# usb_hub.net
KiCad netlist of a schematic drawn in Altium Designer
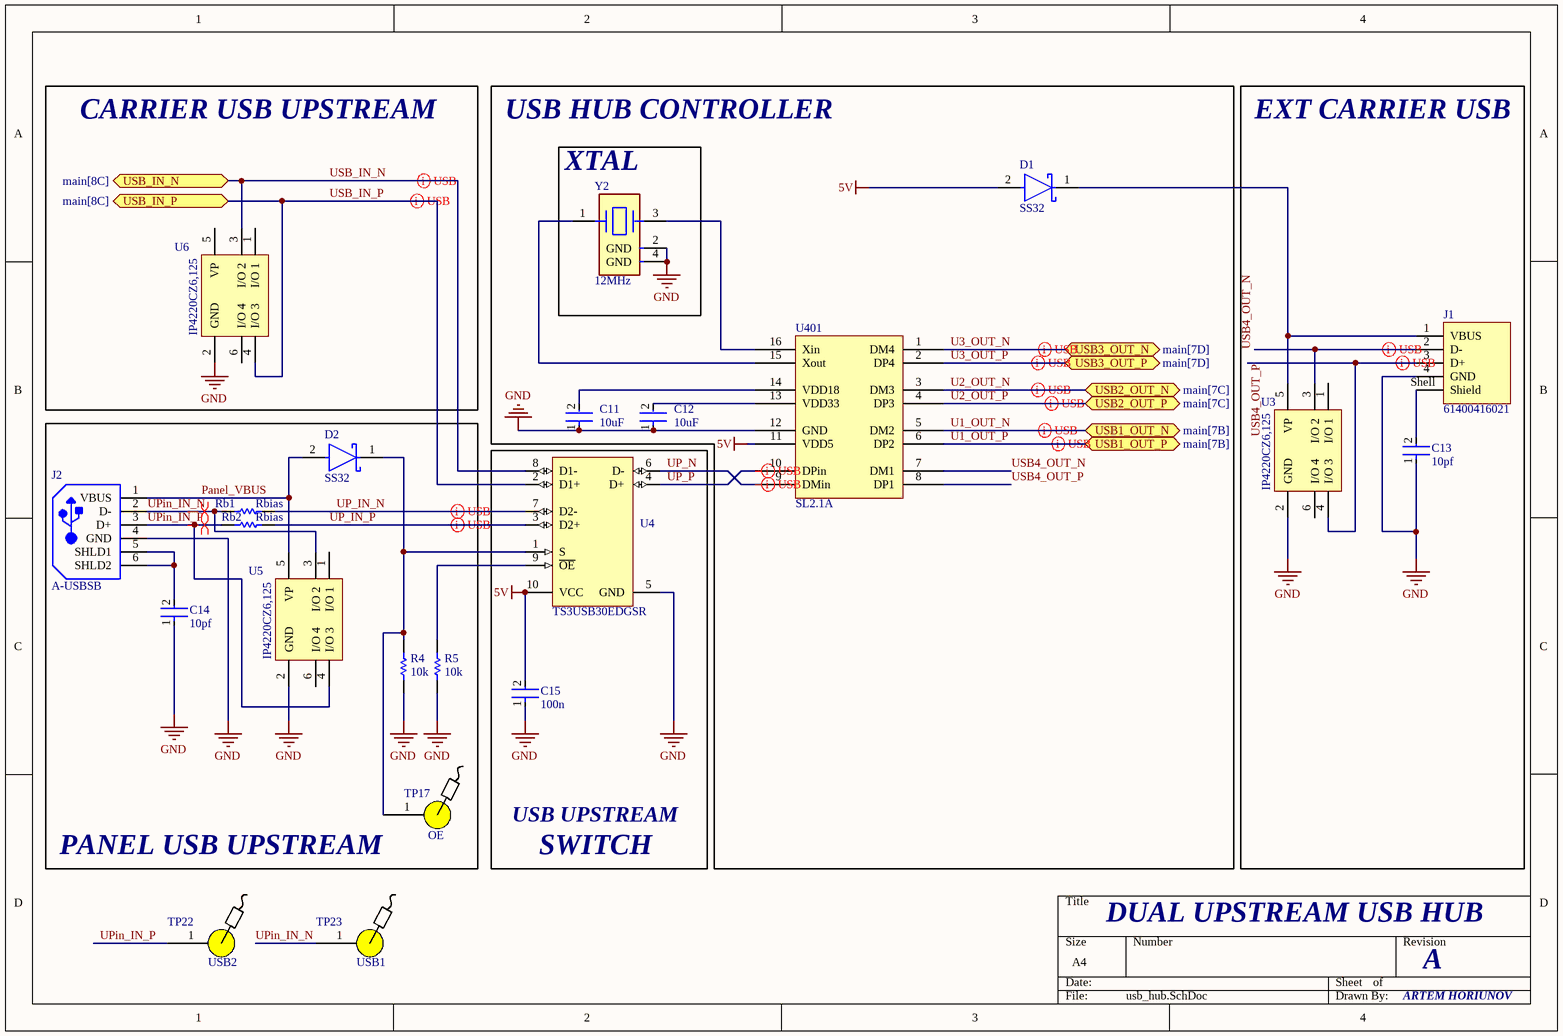
[diagram p0: usb_hub.SchDoc]

(export (version "E")
  (design (tool "Eeschema 10.0.6"))
  (components
    (comp (ref "C11")
      (value "10uF")
      (footprint "FP-C0603C-CF-MFG")
      (description "CAP CER 0.1UF 50V X7R 0603")
      (fields (field (name "TOLERANCE") "0.1") (field (name "MANUFACTURER") "KEMET"))
      (libsource (lib "Altium Content Vault") (part "b4654b650e69147ec39a6b967a45e02"))
    )
    (comp (ref "C12")
      (value "10uF")
      (footprint "FP-C0603C-CF-MFG")
      (description "CAP CER 0.1UF 50V X7R 0603")
      (fields (field (name "TOLERANCE") "0.1") (field (name "MANUFACTURER") "KEMET"))
      (libsource (lib "Altium Content Vault") (part "b4654b650e69147ec39a6b967a45e02"))
    )
    (comp (ref "C13")
      (value "10pf")
      (footprint "FP-C0603C-CF-MFG")
      (description "CAP CER 0.1UF 50V X7R 0603")
      (fields (field (name "TOLERANCE") "0.1") (field (name "MANUFACTURER") "KEMET"))
      (libsource (lib "Altium Content Vault") (part "b4654b650e69147ec39a6b967a45e02"))
    )
    (comp (ref "C14")
      (value "10pf")
      (footprint "FP-C0603C-CF-MFG")
      (description "CAP CER 0.1UF 50V X7R 0603")
      (fields (field (name "TOLERANCE") "0.1") (field (name "MANUFACTURER") "KEMET"))
      (libsource (lib "Altium Content Vault") (part "b4654b650e69147ec39a6b967a45e02"))
    )
    (comp (ref "C15")
      (value "100n")
      (footprint "FP-C0603C-CF-MFG")
      (description "CAP CER 0.1UF 50V X7R 0603")
      (fields (field (name "TOLERANCE") "0.1") (field (name "MANUFACTURER") "KEMET"))
      (libsource (lib "Altium Content Vault") (part "b4654b650e69147ec39a6b967a45e02"))
    )
    (comp (ref "D1")
      (value "SS32")
      (footprint "FP-403AG-MFG")
      (description "SS32 Rectifier Diode, Schottky, 1 Phase, 1 Element, 3A, 20V V(RRM), Silicon, DO-214AB")
      (libsource (lib "Altium Content Vault") (part "c1678fac7984e62e0809fbf79c06691"))
    )
    (comp (ref "D2")
      (value "SS32")
      (footprint "FP-403AG-MFG")
      (description "SS32 Rectifier Diode, Schottky, 1 Phase, 1 Element, 3A, 20V V(RRM), Silicon, DO-214AB")
      (libsource (lib "Altium Content Vault") (part "c1678fac7984e62e0809fbf79c06691"))
    )
    (comp (ref "J1")
      (value "61400416021")
      (footprint "61400416021")
      (libsource (lib "Altium Content Vault") (part "USB 2.0_Type A_Receptacle_1 Port"))
    )
    (comp (ref "J2")
      (value "A-USBSB")
      (footprint "ASSM-A-USBSB-4_V")
      (description "Connector Receptacle, USB Type B, Right Angle, -20 to 85 degC, 4-Pin THD, RoHS, Tray")
      (fields (field (name "MANUFACTURER") "ASSMANN WSW"))
      (libsource (lib "Altium Content Vault") (part "USB-4-2SHLD"))
    )
    (comp (ref "R4")
      (value "10k")
      (footprint "RESC0603(1608)_N")
      (description "0.1W 1% 0603 (1608 Metric)  SMD")
      (fields (field (name "TOLERANCE") "5 %") (field (name "POWER") "0.1 W"))
      (libsource (lib "Altium Content Vault") (part "RES"))
    )
    (comp (ref "R5")
      (value "10k")
      (footprint "RESC0603(1608)_N")
      (description "0.1W 1% 0603 (1608 Metric)  SMD")
      (fields (field (name "TOLERANCE") "5 %") (field (name "POWER") "0.1 W"))
      (libsource (lib "Altium Content Vault") (part "RES"))
    )
    (comp (ref "Rb1")
      (value "Rbias")
      (footprint "RESC1005X40X25NL05T05")
      (fields (field (name "PART NUMBER") "CRCW040210R0FKED") (field (name "MANUFACTURER") "Vishay Dale"))
      (libsource (lib "Altium Content Vault") (part "RES"))
    )
    (comp (ref "Rb2")
      (value "Rbias")
      (footprint "RESC1005X40X25NL05T05")
      (fields (field (name "PART NUMBER") "CRCW040210R0FKED") (field (name "MANUFACTURER") "Vishay Dale"))
      (libsource (lib "Altium Content Vault") (part "RES"))
    )
    (comp (ref "TP17") (value "OE") (footprint "TestPoint") (libsource (lib "TestPoint") (part "TestPoint")))
    (comp (ref "TP22")
      (value "USB2")
      (footprint "TestPoint")
      (libsource (lib "TestPoint") (part "TestPoint"))
    )
    (comp (ref "TP23")
      (value "USB1")
      (footprint "TestPoint")
      (libsource (lib "TestPoint") (part "TestPoint"))
    )
    (comp (ref "U3")
      (value "IP4220CZ6,125")
      (footprint "NXP-SOT457_L")
      (fields (field (name "PARTNUMBER") "IP4220CZ6") (field (name "MANUFACTURER") "NXP Semiconductors"))
      (libsource (lib "Altium Content Vault") (part "NXP-IP4220CZ6-6"))
    )
    (comp (ref "U4")
      (value "TS3USB30EDGSR")
      (footprint "DGS0010A_N")
      (fields (field (name "MANUFACTURER") "Texas Instruments"))
      (libsource (lib "Altium Content Vault") (part "TI-TS3USB30E-MSOP_DGS-10"))
    )
    (comp (ref "U5")
      (value "IP4220CZ6,125")
      (footprint "NXP-SOT457_L")
      (fields (field (name "PARTNUMBER") "IP4220CZ6") (field (name "MANUFACTURER") "NXP Semiconductors"))
      (libsource (lib "Altium Content Vault") (part "NXP-IP4220CZ6-6"))
    )
    (comp (ref "U6")
      (value "IP4220CZ6,125")
      (footprint "NXP-SOT457_L")
      (fields (field (name "PARTNUMBER") "IP4220CZ6") (field (name "MANUFACTURER") "NXP Semiconductors"))
      (libsource (lib "Altium Content Vault") (part "NXP-IP4220CZ6-6"))
    )
    (comp (ref "U401")
      (value "SL2.1A")
      (footprint "SOIC127P600X160-16N")
      (libsource (lib "SL21") (part "SL2.1A"))
    )
    (comp (ref "Y2")
      (value "12MHz")
      (footprint "FP-7M-MFG")
      (description "Crystal")
      (fields (field (name "TOLERANCE") "10ppm"))
      (libsource (lib "Altium Content Vault") (part "41079aabb0e87794b56622915be14ed"))
    )
  )
  (nets
    (net (code "1") (name "/Panel_VBUS") (class "Default")
      (node (ref "D2") (pin "2") (pinfunction "A_2") (pintype "passive"))
      (node (ref "J2") (pin "1") (pinfunction "VBUS_1") (pintype "passive"))
      (node (ref "U5") (pin "5") (pinfunction "VP_5") (pintype "power_in"))
    )
    (net (code "2") (name "/U1_OUT_N") (class "Default")
      (node (ref "U401") (pin "5") (pinfunction "DM2_5") (pintype "passive"))
    )
    (net (code "3") (name "/U1_OUT_P") (class "Default")
      (node (ref "U401") (pin "6") (pinfunction "DP2_6") (pintype "passive"))
    )
    (net (code "4") (name "/U2_OUT_N") (class "Default")
      (node (ref "U401") (pin "3") (pinfunction "DM3_3") (pintype "passive"))
    )
    (net (code "5") (name "/U2_OUT_P") (class "Default")
      (node (ref "U401") (pin "4") (pinfunction "DP3_4") (pintype "passive"))
    )
    (net (code "6") (name "/U3_OUT_N") (class "Default")
      (node (ref "U401") (pin "1") (pinfunction "DM4_1") (pintype "passive"))
    )
    (net (code "7") (name "/U3_OUT_P") (class "Default")
      (node (ref "U401") (pin "2") (pinfunction "DP4_2") (pintype "passive"))
    )
    (net (code "8") (name "/UP_IN_N") (class "Default")
      (node (ref "Rb1") (pin "2") (pinfunction "2_2") (pintype "passive"))
      (node (ref "U4") (pin "7") (pinfunction "D2-_7") (pintype "bidirectional"))
    )
    (net (code "9") (name "/UP_IN_P") (class "Default")
      (node (ref "Rb2") (pin "2") (pinfunction "2_2") (pintype "passive"))
      (node (ref "U4") (pin "3") (pinfunction "D2+_3") (pintype "bidirectional"))
    )
    (net (code "10") (name "/UP_N") (class "Default")
      (node (ref "U4") (pin "6") (pinfunction "D-_6") (pintype "bidirectional"))
      (node (ref "U401") (pin "9") (pinfunction "DMin_9") (pintype "passive"))
    )
    (net (code "11") (name "/UP_P") (class "Default")
      (node (ref "U4") (pin "4") (pinfunction "D+_4") (pintype "bidirectional"))
      (node (ref "U401") (pin "10") (pinfunction "DPin_10") (pintype "passive"))
    )
    (net (code "12") (name "/UPin_IN_N") (class "Default")
      (node (ref "J2") (pin "2") (pinfunction "D-_2") (pintype "passive"))
      (node (ref "Rb1") (pin "1") (pinfunction "1_1") (pintype "passive"))
      (node (ref "TP23") (pin "1") (pintype "passive"))
      (node (ref "U5") (pin "3") (pinfunction "I/O_2_3") (pintype "passive"))
    )
    (net (code "13") (name "/UPin_IN_P") (class "Default")
      (node (ref "J2") (pin "3") (pinfunction "D+_3") (pintype "passive"))
      (node (ref "Rb2") (pin "1") (pinfunction "1_1") (pintype "passive"))
      (node (ref "TP22") (pin "1") (pintype "passive"))
      (node (ref "U5") (pin "4") (pinfunction "I/O_3_4") (pintype "passive"))
    )
    (net (code "14") (name "/USB4_OUT_N") (class "Default")
      (node (ref "J1") (pin "2") (pinfunction "D-_2") (pintype "passive"))
      (node (ref "U3") (pin "3") (pinfunction "I/O_2_3") (pintype "passive"))
      (node (ref "U401") (pin "7") (pinfunction "DM1_7") (pintype "passive"))
    )
    (net (code "15") (name "/USB4_OUT_P") (class "Default")
      (node (ref "J1") (pin "3") (pinfunction "D+_3") (pintype "passive"))
      (node (ref "U3") (pin "4") (pinfunction "I/O_3_4") (pintype "passive"))
      (node (ref "U401") (pin "8") (pinfunction "DP1_8") (pintype "passive"))
    )
    (net (code "16") (name "/USB_IN_N") (class "Default")
      (node (ref "U4") (pin "8") (pinfunction "D1-_8") (pintype "bidirectional"))
      (node (ref "U6") (pin "3") (pinfunction "I/O_2_3") (pintype "passive"))
    )
    (net (code "17") (name "/USB_IN_P") (class "Default")
      (node (ref "U4") (pin "2") (pinfunction "D1+_2") (pintype "bidirectional"))
      (node (ref "U6") (pin "4") (pinfunction "I/O_3_4") (pintype "passive"))
    )
    (net (code "18") (name "5V") (class "Default")
      (node (ref "C15") (pin "2") (pinfunction "2_2") (pintype "passive"))
      (node (ref "D1") (pin "2") (pinfunction "A_2") (pintype "passive"))
      (node (ref "U4") (pin "10") (pinfunction "VCC_10") (pintype "power_in"))
      (node (ref "U401") (pin "11") (pinfunction "VDD5_11") (pintype "passive"))
    )
    (net (code "19") (name "GND") (class "Default")
      (node (ref "C11") (pin "1") (pinfunction "1_1") (pintype "passive"))
      (node (ref "C12") (pin "1") (pinfunction "1_1") (pintype "passive"))
      (node (ref "C13") (pin "1") (pinfunction "1_1") (pintype "passive"))
      (node (ref "C14") (pin "1") (pinfunction "1_1") (pintype "passive"))
      (node (ref "C15") (pin "1") (pinfunction "1_1") (pintype "passive"))
      (node (ref "J1") (pin "4") (pinfunction "GND_4") (pintype "passive"))
      (node (ref "J2") (pin "4") (pinfunction "GND_4") (pintype "passive"))
      (node (ref "R4") (pin "1") (pinfunction "1_1") (pintype "passive"))
      (node (ref "R5") (pin "1") (pinfunction "1_1") (pintype "passive"))
      (node (ref "U3") (pin "2") (pinfunction "GND_2") (pintype "power_in"))
      (node (ref "U4") (pin "5") (pinfunction "GND_5") (pintype "power_in"))
      (node (ref "U401") (pin "12") (pinfunction "GND_12") (pintype "passive"))
      (node (ref "U5") (pin "2") (pinfunction "GND_2") (pintype "power_in"))
      (node (ref "U6") (pin "2") (pinfunction "GND_2") (pintype "power_in"))
      (node (ref "Y2") (pin "2") (pinfunction "GND_2") (pintype "power_in"))
      (node (ref "Y2") (pin "4") (pinfunction "GND_4") (pintype "power_in"))
    )
    (net (code "20") (name "Net-(D1-C)") (class "Default")
      (node (ref "D1") (pin "1") (pinfunction "C_1") (pintype "passive"))
      (node (ref "J1") (pin "1") (pinfunction "VBUS_1") (pintype "passive"))
      (node (ref "U3") (pin "5") (pinfunction "VP_5") (pintype "power_in"))
    )
    (net (code "21") (name "Net-(D2-C)") (class "Default")
      (node (ref "D2") (pin "1") (pinfunction "C_1") (pintype "passive"))
      (node (ref "R4") (pin "2") (pinfunction "2_2") (pintype "passive"))
      (node (ref "TP17") (pin "1") (pintype "passive"))
      (node (ref "U4") (pin "1") (pinfunction "S_1") (pintype "input"))
    )
    (net (code "22") (name "Net-(J1-Shield)") (class "Default")
      (node (ref "C13") (pin "2") (pinfunction "2_2") (pintype "passive"))
      (node (ref "J1") (pin "Shell") (pinfunction "Shield_Shell") (pintype "passive"))
    )
    (net (code "23") (name "Net-(J2-SHLD1)") (class "Default")
      (node (ref "C14") (pin "2") (pinfunction "2_2") (pintype "passive"))
      (node (ref "J2") (pin "5") (pinfunction "SHLD1_5") (pintype "passive"))
      (node (ref "J2") (pin "6") (pinfunction "SHLD2_6") (pintype "passive"))
    )
    (net (code "24") (name "Net-(U4-~{OE})") (class "Default")
      (node (ref "R5") (pin "2") (pinfunction "2_2") (pintype "passive"))
      (node (ref "U4") (pin "9") (pinfunction "~{OE}_9") (pintype "input"))
    )
    (net (code "25") (name "Net-(U401-VDD18)") (class "Default")
      (node (ref "C11") (pin "2") (pinfunction "2_2") (pintype "passive"))
      (node (ref "U401") (pin "14") (pinfunction "VDD18_14") (pintype "passive"))
    )
    (net (code "26") (name "Net-(U401-VDD33)") (class "Default")
      (node (ref "C12") (pin "2") (pinfunction "2_2") (pintype "passive"))
      (node (ref "U401") (pin "13") (pinfunction "VDD33_13") (pintype "passive"))
    )
    (net (code "27") (name "Net-(U401-Xin)") (class "Default")
      (node (ref "U401") (pin "16") (pinfunction "Xin_16") (pintype "passive"))
      (node (ref "Y2") (pin "3") (pinfunction "3_3") (pintype "passive"))
    )
    (net (code "28") (name "Net-(U401-Xout)") (class "Default")
      (node (ref "U401") (pin "15") (pinfunction "Xout_15") (pintype "passive"))
      (node (ref "Y2") (pin "1") (pinfunction "1_1") (pintype "passive"))
    )
    (net (code "29") (name "unconnected-(U3-I{slash}O_1-Pad1)") (class "Default")
      (node (ref "U3") (pin "1") (pinfunction "I/O_1_1") (pintype "passive"))
    )
    (net (code "30") (name "unconnected-(U3-I{slash}O_4-Pad6)") (class "Default")
      (node (ref "U3") (pin "6") (pinfunction "I/O_4_6") (pintype "passive"))
    )
    (net (code "31") (name "unconnected-(U5-I{slash}O_1-Pad1)") (class "Default")
      (node (ref "U5") (pin "1") (pinfunction "I/O_1_1") (pintype "passive"))
    )
    (net (code "32") (name "unconnected-(U5-I{slash}O_4-Pad6)") (class "Default")
      (node (ref "U5") (pin "6") (pinfunction "I/O_4_6") (pintype "passive"))
    )
    (net (code "33") (name "unconnected-(U6-I{slash}O_1-Pad1)") (class "Default")
      (node (ref "U6") (pin "1") (pinfunction "I/O_1_1") (pintype "passive"))
    )
    (net (code "34") (name "unconnected-(U6-I{slash}O_4-Pad6)") (class "Default")
      (node (ref "U6") (pin "6") (pinfunction "I/O_4_6") (pintype "passive"))
    )
    (net (code "35") (name "unconnected-(U6-VP-Pad5)") (class "Default")
      (node (ref "U6") (pin "5") (pinfunction "VP_5") (pintype "power_in"))
    )
  )
)
